# PAGE15_FLASH.net
KiCad netlist of a schematic drawn in Altium Designer
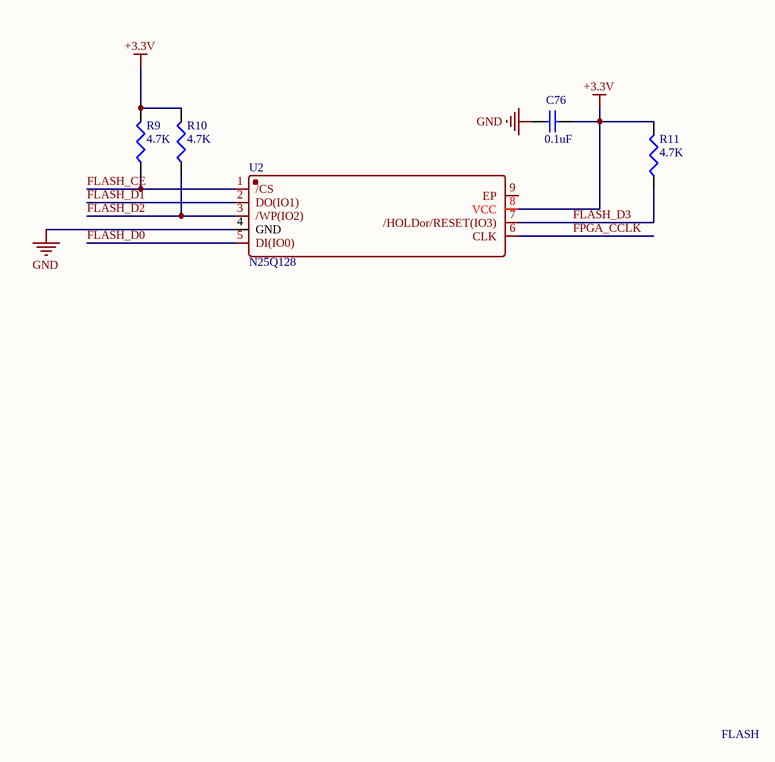
[diagram p0: PAGE15 FLASH.SchDoc]

(export (version "E")
  (design (tool "Eeschema 10.0.6"))
  (components
    (comp (ref "C76")
      (value "0.1uF")
      (footprint "0402")
      (description "Capacitor (Semiconductor SIM Model)")
      (fields (field (name "Comment") "Cap Semi") (field (name "PUBLISHER") "Altium Limited"))
      (libsource (lib "Miscellaneous Devices") (part "Cap Semi"))
    )
    (comp (ref "R9")
      (value "4.7K")
      (footprint "J1-0603")
      (description "Resistor")
      (fields (field (name "Comment") "Res3") (field (name "PUBLISHER") "Altium Limited"))
      (libsource (lib "Miscellaneous Devices") (part "Res3"))
    )
    (comp (ref "R10")
      (value "4.7K")
      (footprint "J1-0603")
      (description "Resistor")
      (fields (field (name "Comment") "Res3") (field (name "PUBLISHER") "Altium Limited"))
      (libsource (lib "Miscellaneous Devices") (part "Res3"))
    )
    (comp (ref "R11")
      (value "4.7K")
      (footprint "J1-0603")
      (description "Resistor")
      (fields (field (name "Comment") "Res3") (field (name "PUBLISHER") "Altium Limited"))
      (libsource (lib "Miscellaneous Devices") (part "Res3"))
    )
    (comp (ref "U2")
      (value "N25Q128")
      (footprint "WSON-8_L6.0-W8.0-P1.27-BL-EP")
      (libsource (lib "Schlib1") (part "N25Q128"))
    )
  )
  (nets
    (net (code "1") (name "+3.3V") (class "Default")
      (node (ref "C76") (pin "2") (pinfunction "2_2") (pintype "passive"))
      (node (ref "R10") (pin "2") (pinfunction "2_2") (pintype "passive"))
      (node (ref "R11") (pin "2") (pinfunction "2_2") (pintype "passive"))
      (node (ref "R9") (pin "2") (pinfunction "2_2") (pintype "passive"))
      (node (ref "U2") (pin "8") (pinfunction "VCC_8") (pintype "passive"))
    )
    (net (code "2") (name "/FLASH_CE") (class "Default")
      (node (ref "R9") (pin "1") (pinfunction "1_1") (pintype "passive"))
      (node (ref "U2") (pin "1") (pinfunction "/CS_1") (pintype "passive"))
    )
    (net (code "3") (name "/FLASH_D0") (class "Default")
      (node (ref "U2") (pin "5") (pinfunction "DI(IO0)_5") (pintype "passive"))
    )
    (net (code "4") (name "/FLASH_D1") (class "Default")
      (node (ref "U2") (pin "2") (pinfunction "DO(IO1)_2") (pintype "passive"))
    )
    (net (code "5") (name "/FLASH_D2") (class "Default")
      (node (ref "R10") (pin "1") (pinfunction "1_1") (pintype "passive"))
      (node (ref "U2") (pin "3") (pinfunction "/WP(IO2)_3") (pintype "passive"))
    )
    (net (code "6") (name "/FLASH_D3") (class "Default")
      (node (ref "R11") (pin "1") (pinfunction "1_1") (pintype "passive"))
      (node (ref "U2") (pin "7") (pinfunction "/HOLDor/RESET(IO3)_7") (pintype "passive"))
    )
    (net (code "7") (name "/FPGA_CCLK") (class "Default")
      (node (ref "U2") (pin "6") (pinfunction "CLK_6") (pintype "passive"))
    )
    (net (code "8") (name "GND") (class "Default")
      (node (ref "C76") (pin "1") (pinfunction "1_1") (pintype "passive"))
      (node (ref "U2") (pin "4") (pinfunction "GND_4") (pintype "passive"))
    )
    (net (code "9") (name "unconnected-(U2-EP-Pad9)") (class "Default")
      (node (ref "U2") (pin "9") (pinfunction "EP_9") (pintype "passive"))
    )
  )
)
